# Umwandlung_1_8_to_5.net
KiCad netlist of a schematic drawn in EAGLE
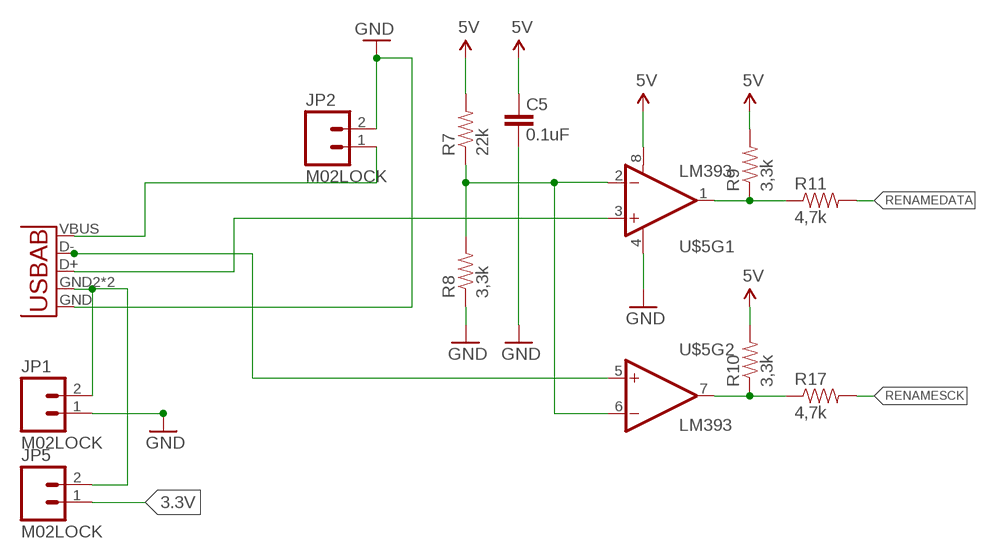
[diagram p0: schematic, sheet 1]

(export (version "E")
  (design (tool "Eeschema 10.0.6"))
  (components
    (comp (ref "C5")
      (value "0.1uF")
      (footprint "eagle-import:0805")
      (libsource (lib "eagle-import") (part "CAP0805"))
    )
    (comp (ref "JP1")
      (value "M02LOCK")
      (footprint "eagle-import:1X02_LOCK")
      (libsource (lib "eagle-import") (part "M02LOCK"))
    )
    (comp (ref "JP2")
      (value "M02LOCK")
      (footprint "eagle-import:1X02_LOCK")
      (libsource (lib "eagle-import") (part "M02LOCK"))
    )
    (comp (ref "JP5")
      (value "M02LOCK")
      (footprint "eagle-import:1X02_LOCK")
      (libsource (lib "eagle-import") (part "M02LOCK"))
    )
    (comp (ref "R7")
      (value "22k")
      (footprint "eagle-import:0805")
      (libsource (lib "eagle-import") (part "RESISTOR"))
    )
    (comp (ref "R8")
      (value "3,3k")
      (footprint "eagle-import:0805")
      (libsource (lib "eagle-import") (part "RESISTOR"))
    )
    (comp (ref "R9")
      (value "3,3k")
      (footprint "eagle-import:0805")
      (libsource (lib "eagle-import") (part "RESISTOR"))
    )
    (comp (ref "R10")
      (value "3,3k")
      (footprint "eagle-import:0805")
      (libsource (lib "eagle-import") (part "RESISTOR"))
    )
    (comp (ref "R11")
      (value "4,7k")
      (footprint "eagle-import:0805")
      (libsource (lib "eagle-import") (part "RESISTOR"))
    )
    (comp (ref "R17")
      (value "4,7k")
      (footprint "eagle-import:0805")
      (libsource (lib "eagle-import") (part "RESISTOR"))
    )
    (comp (ref "U$5")
      (value "LM393")
      (footprint "eagle-import:SO08")
      (libsource (lib "eagle-import") (part "LM393"))
    )
    (comp (ref "U$7")
      (value "USB-A")
      (footprint "eagle-import:USB-A")
      (libsource (lib "eagle-import") (part "USB-A"))
    )
  )
  (nets
    (net (code "1") (name "3.3V") (class "Default")
      (node (ref "JP5") (pin "1") (pinfunction "1_1") (pintype "passive"))
    )
    (net (code "2") (name "5V") (class "Default")
      (node (ref "C5") (pin "2") (pinfunction "2_2") (pintype "passive"))
      (node (ref "R10") (pin "2") (pinfunction "2_2") (pintype "passive"))
      (node (ref "R7") (pin "2") (pinfunction "2_2") (pintype "passive"))
      (node (ref "R9") (pin "2") (pinfunction "2_2") (pintype "passive"))
      (node (ref "U$5") (pin "8") (pinfunction "V+_8") (pintype "power_in"))
    )
    (net (code "3") (name "GND") (class "Default")
      (node (ref "C5") (pin "1") (pinfunction "1_1") (pintype "passive"))
      (node (ref "JP1") (pin "1") (pinfunction "1_1") (pintype "passive"))
      (node (ref "JP2") (pin "2") (pinfunction "2_2") (pintype "passive"))
      (node (ref "R8") (pin "1") (pinfunction "1_1") (pintype "passive"))
      (node (ref "U$5") (pin "4") (pinfunction "V-_4") (pintype "power_in"))
      (node (ref "U$7") (pin "GND") (pinfunction "GND_GND") (pintype "bidirectional"))
    )
    (net (code "4") (name "Net-(JP1-Pad2)") (class "Default")
      (node (ref "JP1") (pin "2") (pinfunction "2_2") (pintype "passive"))
      (node (ref "JP5") (pin "2") (pinfunction "2_2") (pintype "passive"))
      (node (ref "U$7") (pin "GND2") (pinfunction "USBID_GND2") (pintype "bidirectional"))
      (node (ref "U$7") (pin "GND3") (pinfunction "USBID_GND3") (pintype "bidirectional"))
    )
    (net (code "5") (name "Net-(JP2-Pad1)") (class "Default")
      (node (ref "JP2") (pin "1") (pinfunction "1_1") (pintype "passive"))
      (node (ref "U$7") (pin "VBUS") (pinfunction "VBUS_VBUS") (pintype "bidirectional"))
    )
    (net (code "6") (name "Net-(U$5A-+IN)") (class "Default")
      (node (ref "U$5") (pin "3") (pinfunction "+IN_3") (pintype "input"))
      (node (ref "U$7") (pin "D+") (pinfunction "D+_D+") (pintype "bidirectional"))
    )
    (net (code "7") (name "Net-(U$5A--IN)") (class "Default")
      (node (ref "R7") (pin "1") (pinfunction "1_1") (pintype "passive"))
      (node (ref "R8") (pin "2") (pinfunction "2_2") (pintype "passive"))
      (node (ref "U$5") (pin "2") (pinfunction "-IN_2") (pintype "input"))
      (node (ref "U$5") (pin "6") (pinfunction "-IN_6") (pintype "input"))
    )
    (net (code "8") (name "Net-(U$5A-OUT)") (class "Default")
      (node (ref "R11") (pin "1") (pinfunction "1_1") (pintype "passive"))
      (node (ref "R9") (pin "1") (pinfunction "1_1") (pintype "passive"))
      (node (ref "U$5") (pin "1") (pinfunction "OUT_1") (pintype "output"))
    )
    (net (code "9") (name "Net-(U$5B-+IN)") (class "Default")
      (node (ref "U$5") (pin "5") (pinfunction "+IN_5") (pintype "input"))
      (node (ref "U$7") (pin "D-") (pinfunction "D-_D-") (pintype "bidirectional"))
    )
    (net (code "10") (name "Net-(U$5B-OUT)") (class "Default")
      (node (ref "R10") (pin "1") (pinfunction "1_1") (pintype "passive"))
      (node (ref "R17") (pin "1") (pinfunction "1_1") (pintype "passive"))
      (node (ref "U$5") (pin "7") (pinfunction "OUT_7") (pintype "output"))
    )
    (net (code "11") (name "RENAMEDATA") (class "Default")
      (node (ref "R11") (pin "2") (pinfunction "2_2") (pintype "passive"))
    )
    (net (code "12") (name "RENAMESCK") (class "Default")
      (node (ref "R17") (pin "2") (pinfunction "2_2") (pintype "passive"))
    )
  )
)
